# power.net
KiCad netlist of a schematic drawn in Altium Designer
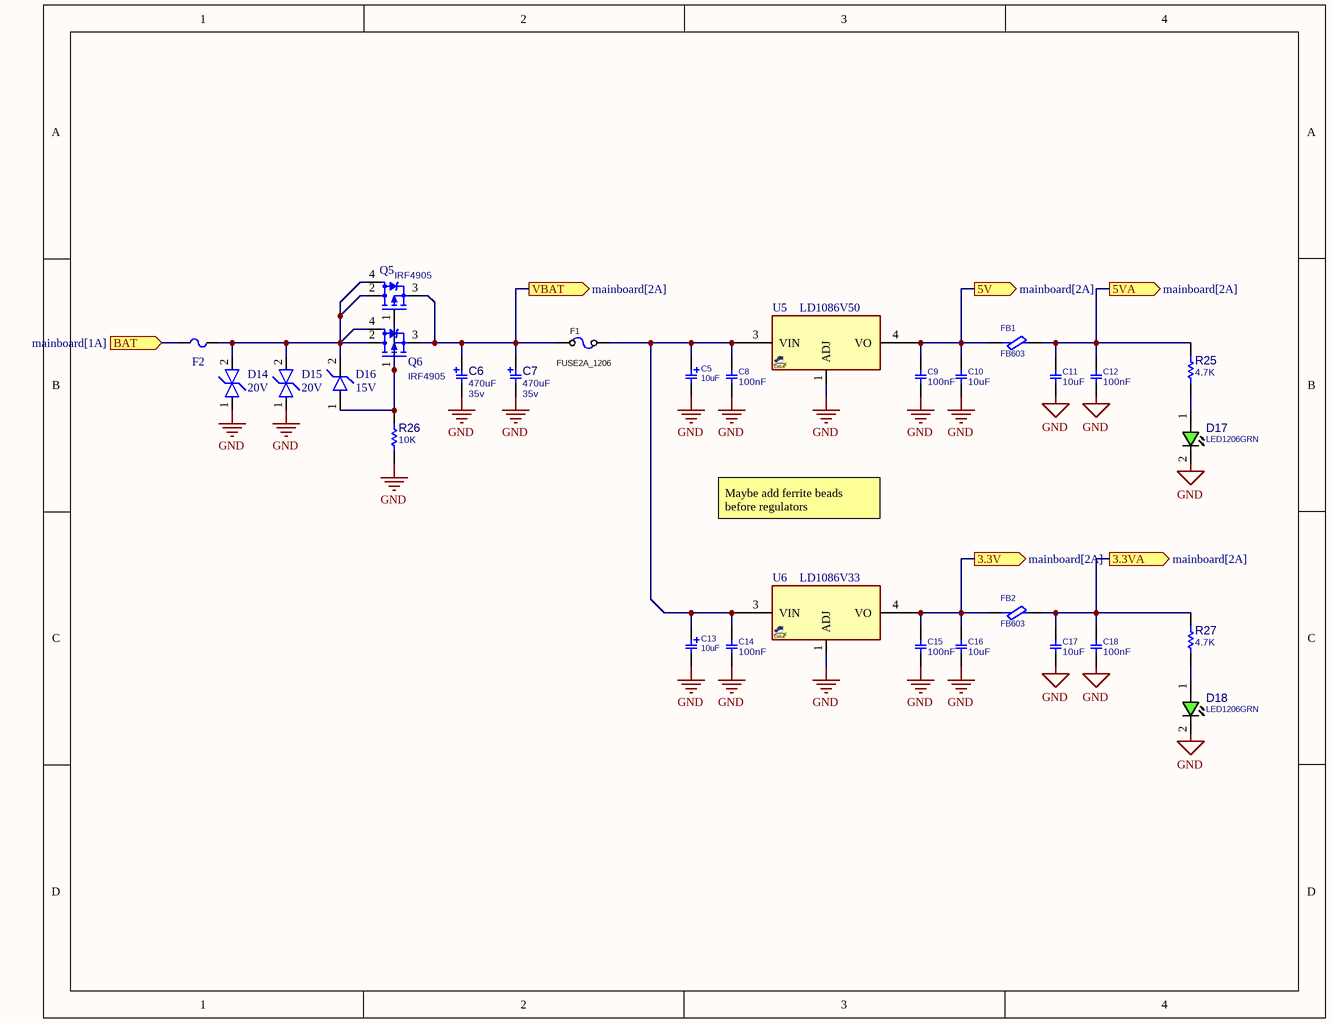
[diagram p0: power.SchDoc]

(export (version "E")
  (design (tool "Eeschema 10.0.6"))
  (components
    (comp (ref "C5")
      (value "10uF")
      (footprint "C_TN_7343")
      (description "CAP, SMD, TAN")
      (fields (field (name "MANF") "VISHAY") (field (name "MANF_P#") "593D106X9035D2TE3"))
      (libsource (lib "passive_smd") (part "CAP_SMD_TAN_10uF_35V"))
    )
    (comp (ref "C6")
      (value "470uF")
      (footprint "C_EL_D10L10")
      (description "CAP, SMD, ELEC,")
      (fields
        (field (name "MANF_P#") "MANF_PART#")
        (field (name "MANF") "MANF")
        (field (name "PARAM2") "35v")
      )
      (libsource (lib "passive_smd") (part "CAP_SMD_EL_470uF_35v"))
    )
    (comp (ref "C7")
      (value "470uF")
      (footprint "C_EL_D10L10")
      (description "CAP, SMD, ELEC,")
      (fields
        (field (name "MANF_P#") "MANF_PART#")
        (field (name "MANF") "MANF")
        (field (name "PARAM2") "35v")
      )
      (libsource (lib "passive_smd") (part "CAP_SMD_EL_470uF_35v"))
    )
    (comp (ref "C8")
      (value "100nF")
      (footprint "C1206")
      (description "CAP, MLCC")
      (fields (field (name "MANF_P#") "MANF_PART#"))
      (libsource (lib "passive_smd") (part "CAP_SMD_MLCC_1206"))
    )
    (comp (ref "C9")
      (value "100nF")
      (footprint "C1206")
      (description "CAP, MLCC")
      (fields (field (name "MANF_P#") "MANF_PART#"))
      (libsource (lib "passive_smd") (part "CAP_SMD_MLCC_1206"))
    )
    (comp (ref "C10")
      (value "10uF")
      (footprint "C1206")
      (description "CAP, MLCC")
      (fields (field (name "MANF_P#") "MANF_PART#") (field (name "MANF") "Murata"))
      (libsource (lib "passive_smd") (part "CAP_SMD_MLCC"))
    )
    (comp (ref "C11")
      (value "10uF")
      (footprint "C1206")
      (description "CAP, MLCC")
      (fields (field (name "MANF_P#") "MANF_PART#") (field (name "MANF") "Murata"))
      (libsource (lib "passive_smd") (part "CAP_SMD_MLCC"))
    )
    (comp (ref "C12")
      (value "100nF")
      (footprint "C1206")
      (description "CAP, MLCC")
      (fields (field (name "MANF_P#") "MANF_PART#"))
      (libsource (lib "passive_smd") (part "CAP_SMD_MLCC_1206"))
    )
    (comp (ref "C13")
      (value "10uF")
      (footprint "C_TN_7343")
      (description "CAP, SMD, TAN")
      (fields (field (name "MANF") "VISHAY") (field (name "MANF_P#") "593D106X9035D2TE3"))
      (libsource (lib "passive_smd") (part "CAP_SMD_TAN_10uF_35V"))
    )
    (comp (ref "C14")
      (value "100nF")
      (footprint "C1206")
      (description "CAP, MLCC")
      (fields (field (name "MANF_P#") "MANF_PART#"))
      (libsource (lib "passive_smd") (part "CAP_SMD_MLCC_1206"))
    )
    (comp (ref "C15")
      (value "100nF")
      (footprint "C1206")
      (description "CAP, MLCC")
      (fields (field (name "MANF_P#") "MANF_PART#"))
      (libsource (lib "passive_smd") (part "CAP_SMD_MLCC_1206"))
    )
    (comp (ref "C16")
      (value "10uF")
      (footprint "C1206")
      (description "CAP, MLCC")
      (fields (field (name "MANF_P#") "MANF_PART#") (field (name "MANF") "Murata"))
      (libsource (lib "passive_smd") (part "CAP_SMD_MLCC"))
    )
    (comp (ref "C17")
      (value "10uF")
      (footprint "C1206")
      (description "CAP, MLCC")
      (fields (field (name "MANF_P#") "MANF_PART#") (field (name "MANF") "Murata"))
      (libsource (lib "passive_smd") (part "CAP_SMD_MLCC"))
    )
    (comp (ref "C18")
      (value "100nF")
      (footprint "C1206")
      (description "CAP, MLCC")
      (fields (field (name "MANF_P#") "MANF_PART#"))
      (libsource (lib "passive_smd") (part "CAP_SMD_MLCC_1206"))
    )
    (comp (ref "D14")
      (value "20V")
      (footprint "FP-SMBJ-CA-MFG")
      (description "TVS DIODE")
      (libsource (lib "Alib") (part "TVS"))
    )
    (comp (ref "D15")
      (value "20V")
      (footprint "FP-SMBJ-CA-MFG")
      (description "TVS DIODE")
      (libsource (lib "Alib") (part "TVS"))
    )
    (comp (ref "D16") (value "15V") (footprint "D_SOD80") (libsource (lib "Alib") (part "Zener-SOD-80")))
    (comp (ref "D17")
      (value "LED1206GRN")
      (footprint "LED1206GRN")
      (description "LED, SMD, 1206, GREEN")
      (libsource (lib "led(diode)") (part "LED_SMD_1206_GRN"))
    )
    (comp (ref "D18")
      (value "LED1206GRN")
      (footprint "LED1206GRN")
      (description "LED, SMD, 1206, GREEN")
      (libsource (lib "led(diode)") (part "LED_SMD_1206_GRN"))
    )
    (comp (ref "F1")
      (value "FUSE2A_1206")
      (footprint "F1206")
      (description "Fuse, 3A, 32VDC, 1206, SMD, Slow Blow")
      (fields (field (name "MANF") "Bourns") (field (name "MANF_P#") "SF-1206SP300-2"))
      (libsource (lib "protect_tvs_esd_fuse") (part "FUSE_3A_1206_SLOW"))
    )
    (comp (ref "F2")
      (value "F=1.0 A")
      (footprint "FUSE - Double PAD")
      (description "Fuses 5x20")
      (fields (field (name "DESIGNER") "Abbas Basereh"))
      (libsource (lib "Alib") (part "Fuse 5x20 with holdeer pins"))
    )
    (comp (ref "FB1")
      (value "FB603")
      (footprint "L1206")
      (description "FERRITE_Bead, SMD")
      (fields (field (name "MANF") "MURATA") (field (name "MANF_P#") "BLM15AG121SN1D"))
      (libsource (lib "emi_filter") (part "FBEAD_SMD"))
    )
    (comp (ref "FB2")
      (value "FB603")
      (footprint "L1206")
      (description "FERRITE_Bead, SMD")
      (fields (field (name "MANF") "MURATA") (field (name "MANF_P#") "BLM15AG121SN1D"))
      (libsource (lib "emi_filter") (part "FBEAD_SMD"))
    )
    (comp (ref "Q5")
      (value "IRF4905")
      (footprint "D2PAK_3")
      (description "HEXFET Power MOSFET")
      (libsource (lib "transistor_fet") (part "MOSP_IRF4905_D2PAK"))
    )
    (comp (ref "Q6")
      (value "IRF4905")
      (footprint "D2PAK_3")
      (description "HEXFET Power MOSFET")
      (libsource (lib "transistor_fet") (part "MOSP_IRF4905_D2PAK"))
    )
    (comp (ref "R25")
      (value "4.7K")
      (footprint "R1206")
      (description "RESISTOR, SMD")
      (libsource (lib "passive_smd") (part "RES_SMD_1206"))
    )
    (comp (ref "R26")
      (value "10K")
      (footprint "R1206")
      (description "RESISTOR, SMD")
      (libsource (lib "passive_smd") (part "RES_SMD_1206"))
    )
    (comp (ref "R27")
      (value "4.7K")
      (footprint "R1206")
      (description "RESISTOR, SMD")
      (libsource (lib "passive_smd") (part "RES_SMD_1206"))
    )
    (comp (ref "U5")
      (value "LD1086V50")
      (footprint "DPAK_3")
      (description "REG, Linear, LDO1.3, Adj, 1A, TO-252")
      (fields (field (name "MANF_P#") "LD1086DTTR, LD1086D2MTR") (field (name "MANF") "ST"))
      (libsource (lib "pwr_reg_linear_108x") (part "VREG_1086_TO252"))
    )
    (comp (ref "U6")
      (value "LD1086V33")
      (footprint "DPAK_3")
      (description "REG, Linear, LDO1.3, Adj, 1A, TO-252")
      (fields (field (name "MANF_P#") "LD1086DTTR, LD1086D2MTR") (field (name "MANF") "ST"))
      (libsource (lib "pwr_reg_linear_108x") (part "VREG_1086_TO252"))
    )
  )
  (nets
    (net (code "1") (name "/3.3V") (class "Default")
      (node (ref "C15") (pin "2") (pinfunction "2_2") (pintype "passive"))
      (node (ref "C16") (pin "2") (pinfunction "2_2") (pintype "passive"))
      (node (ref "FB2") (pin "2") (pinfunction "2_2") (pintype "passive"))
      (node (ref "U6") (pin "4") (pinfunction "VO_4") (pintype "passive"))
    )
    (net (code "2") (name "/3.3VA") (class "Default")
      (node (ref "C17") (pin "2") (pinfunction "2_2") (pintype "passive"))
      (node (ref "C18") (pin "2") (pinfunction "2_2") (pintype "passive"))
      (node (ref "FB2") (pin "1") (pinfunction "1_1") (pintype "passive"))
      (node (ref "R27") (pin "2") (pinfunction "2_2") (pintype "passive"))
    )
    (net (code "3") (name "/5V") (class "Default")
      (node (ref "C10") (pin "2") (pinfunction "2_2") (pintype "passive"))
      (node (ref "C9") (pin "2") (pinfunction "2_2") (pintype "passive"))
      (node (ref "FB1") (pin "2") (pinfunction "2_2") (pintype "passive"))
      (node (ref "U5") (pin "4") (pinfunction "VO_4") (pintype "passive"))
    )
    (net (code "4") (name "/5VA") (class "Default")
      (node (ref "C11") (pin "2") (pinfunction "2_2") (pintype "passive"))
      (node (ref "C12") (pin "2") (pinfunction "2_2") (pintype "passive"))
      (node (ref "FB1") (pin "1") (pinfunction "1_1") (pintype "passive"))
      (node (ref "R25") (pin "2") (pinfunction "2_2") (pintype "passive"))
    )
    (net (code "5") (name "/BAT") (class "Default")
      (node (ref "F2") (pin "1") (pinfunction "1_1") (pintype "passive"))
    )
    (net (code "6") (name "/VBAT") (class "Default")
      (node (ref "C6") (pin "1") (pinfunction "1_1") (pintype "passive"))
      (node (ref "C7") (pin "1") (pinfunction "1_1") (pintype "passive"))
      (node (ref "F1") (pin "1") (pinfunction "1_1") (pintype "passive"))
      (node (ref "Q5") (pin "3") (pinfunction "S_3") (pintype "passive"))
      (node (ref "Q6") (pin "3") (pinfunction "S_3") (pintype "passive"))
    )
    (net (code "7") (name "GND") (class "Default")
      (node (ref "C10") (pin "1") (pinfunction "1_1") (pintype "passive"))
      (node (ref "C11") (pin "1") (pinfunction "1_1") (pintype "passive"))
      (node (ref "C12") (pin "1") (pinfunction "1_1") (pintype "passive"))
      (node (ref "C13") (pin "2") (pinfunction "2_2") (pintype "passive"))
      (node (ref "C14") (pin "1") (pinfunction "1_1") (pintype "passive"))
      (node (ref "C15") (pin "1") (pinfunction "1_1") (pintype "passive"))
      (node (ref "C16") (pin "1") (pinfunction "1_1") (pintype "passive"))
      (node (ref "C17") (pin "1") (pinfunction "1_1") (pintype "passive"))
      (node (ref "C18") (pin "1") (pinfunction "1_1") (pintype "passive"))
      (node (ref "C5") (pin "2") (pinfunction "2_2") (pintype "passive"))
      (node (ref "C6") (pin "2") (pinfunction "2_2") (pintype "passive"))
      (node (ref "C7") (pin "2") (pinfunction "2_2") (pintype "passive"))
      (node (ref "C8") (pin "1") (pinfunction "1_1") (pintype "passive"))
      (node (ref "C9") (pin "1") (pinfunction "1_1") (pintype "passive"))
      (node (ref "D14") (pin "1") (pinfunction "1_1") (pintype "passive"))
      (node (ref "D15") (pin "1") (pinfunction "1_1") (pintype "passive"))
      (node (ref "D17") (pin "2") (pinfunction "CATHODE_2") (pintype "passive"))
      (node (ref "D18") (pin "2") (pinfunction "CATHODE_2") (pintype "passive"))
      (node (ref "R26") (pin "1") (pinfunction "1_1") (pintype "passive"))
      (node (ref "U5") (pin "1") (pinfunction "ADJ_1") (pintype "passive"))
      (node (ref "U6") (pin "1") (pinfunction "ADJ_1") (pintype "passive"))
    )
    (net (code "8") (name "Net-(D14-Pad2)") (class "Default")
      (node (ref "D14") (pin "2") (pinfunction "2_2") (pintype "passive"))
      (node (ref "D15") (pin "2") (pinfunction "2_2") (pintype "passive"))
      (node (ref "D16") (pin "2") (pinfunction "2_2") (pintype "passive"))
      (node (ref "F2") (pin "2") (pinfunction "2_2") (pintype "passive"))
      (node (ref "Q5") (pin "2") (pinfunction "D_2") (pintype "passive"))
      (node (ref "Q5") (pin "4") (pinfunction "D_4") (pintype "passive"))
      (node (ref "Q6") (pin "2") (pinfunction "D_2") (pintype "passive"))
      (node (ref "Q6") (pin "4") (pinfunction "D_4") (pintype "passive"))
    )
    (net (code "9") (name "Net-(D17-ANODE)") (class "Default")
      (node (ref "D17") (pin "1") (pinfunction "ANODE_1") (pintype "passive"))
      (node (ref "R25") (pin "1") (pinfunction "1_1") (pintype "passive"))
    )
    (net (code "10") (name "Net-(D18-ANODE)") (class "Default")
      (node (ref "D18") (pin "1") (pinfunction "ANODE_1") (pintype "passive"))
      (node (ref "R27") (pin "1") (pinfunction "1_1") (pintype "passive"))
    )
    (net (code "11") (name "Net-(Q5-G)") (class "Default")
      (node (ref "D16") (pin "1") (pinfunction "1_1") (pintype "passive"))
      (node (ref "Q5") (pin "1") (pinfunction "G_1") (pintype "passive"))
      (node (ref "Q6") (pin "1") (pinfunction "G_1") (pintype "passive"))
      (node (ref "R26") (pin "2") (pinfunction "2_2") (pintype "passive"))
    )
    (net (code "12") (name "Net-(U5-VIN)") (class "Default")
      (node (ref "C13") (pin "1") (pinfunction "1_1") (pintype "passive"))
      (node (ref "C14") (pin "2") (pinfunction "2_2") (pintype "passive"))
      (node (ref "C5") (pin "1") (pinfunction "1_1") (pintype "passive"))
      (node (ref "C8") (pin "2") (pinfunction "2_2") (pintype "passive"))
      (node (ref "F1") (pin "2") (pinfunction "2_2") (pintype "passive"))
      (node (ref "U5") (pin "3") (pinfunction "VIN_3") (pintype "passive"))
      (node (ref "U6") (pin "3") (pinfunction "VIN_3") (pintype "passive"))
    )
  )
)
